# Sheet1.net
KiCad netlist of a schematic drawn in Altium Designer
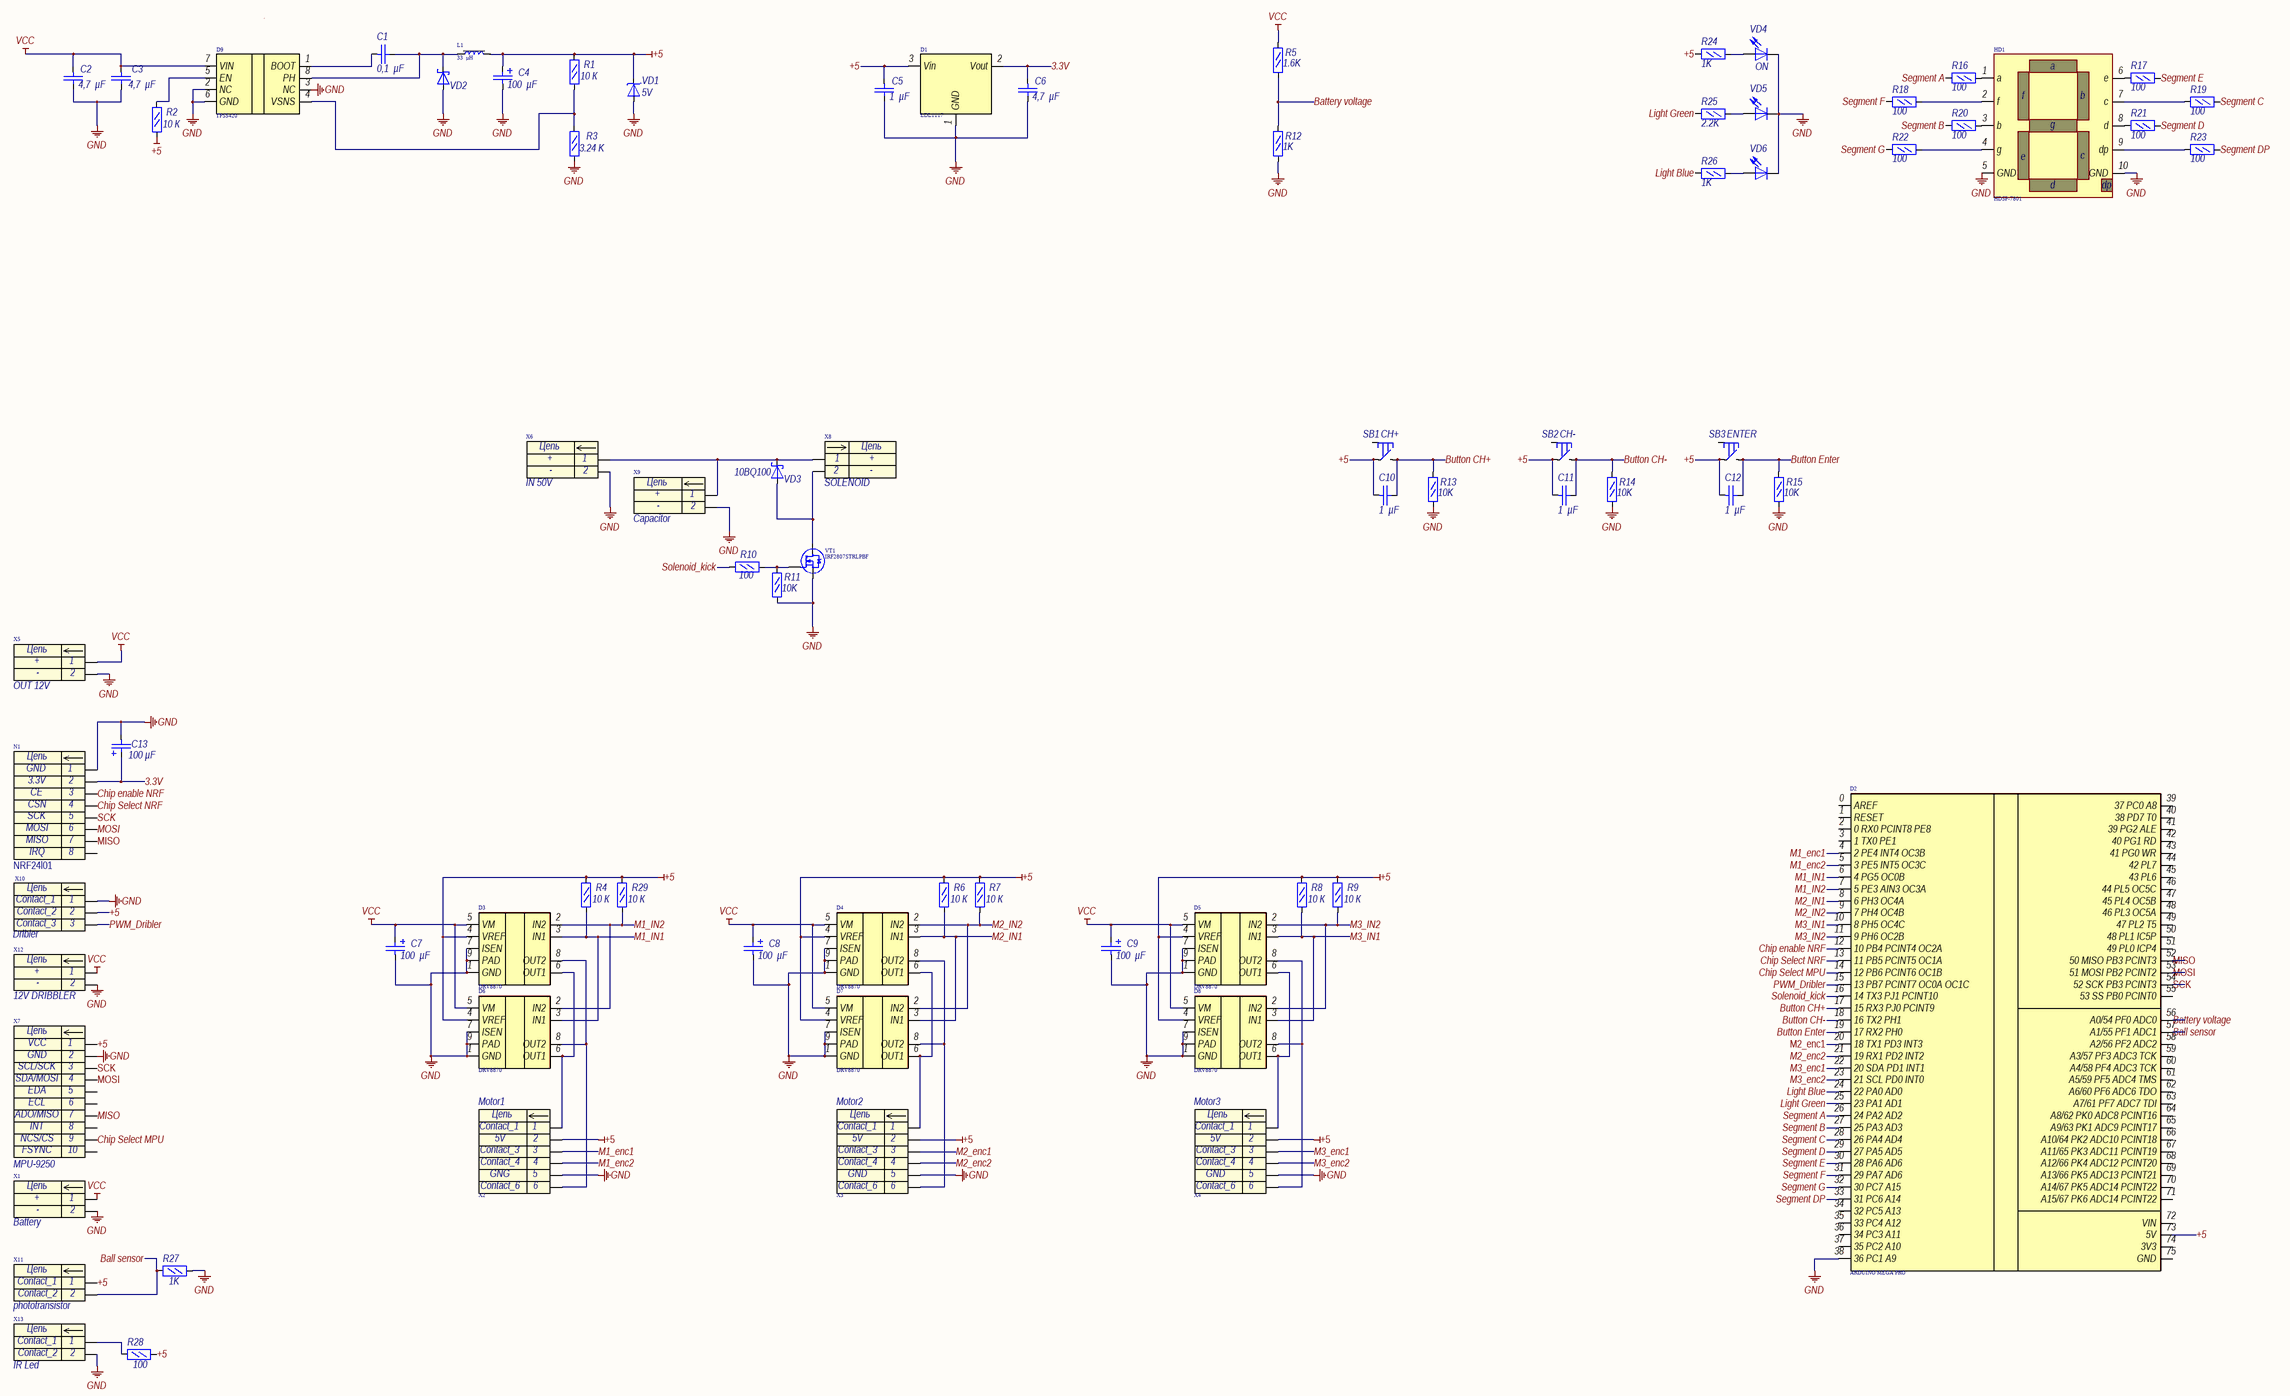
[diagram p0: Sheet1.SchDoc]

(export (version "E")
  (design (tool "Eeschema 10.0.6"))
  (components
    (comp (ref "C1")
      (value "0,1  µF")
      (footprint "LibPCB:NPC0805")
      (description "Конденсатор кер.")
      (libsource (lib "LibSCH") (part "Capacitor ceramic"))
    )
    (comp (ref "C2")
      (value "4,7  µF")
      (footprint "LibPCB:NPC0805")
      (description "Конденсатор кер.")
      (libsource (lib "LibSCH") (part "Capacitor ceramic"))
    )
    (comp (ref "C3")
      (value "4,7  µF")
      (footprint "LibPCB:NPC0805")
      (description "Конденсатор кер.")
      (libsource (lib "LibSCH") (part "Capacitor ceramic"))
    )
    (comp (ref "C4")
      (value "100  µF")
      (footprint "TANTAL CAPACITOR C")
      (description "Конденсатор пол.")
      (libsource (lib "LibSCH") (part "Capacitor tantal"))
    )
    (comp (ref "C5")
      (value "1  µF")
      (footprint "LibPCB:NPC0805")
      (description "Конденсатор кер.")
      (libsource (lib "LibSCH") (part "Capacitor ceramic"))
    )
    (comp (ref "C6")
      (value "4,7  µF")
      (footprint "LibPCB:NPC0805")
      (description "Конденсатор кер.")
      (libsource (lib "LibSCH") (part "Capacitor ceramic"))
    )
    (comp (ref "C7")
      (value "100  µF")
      (footprint "TANTAL CAPACITOR C")
      (description "Конденсатор пол.")
      (libsource (lib "LibSCH") (part "Capacitor tantal"))
    )
    (comp (ref "C8")
      (value "100  µF")
      (footprint "TANTAL CAPACITOR C")
      (description "Конденсатор пол.")
      (libsource (lib "LibSCH") (part "Capacitor tantal"))
    )
    (comp (ref "C9")
      (value "100  µF")
      (footprint "TANTAL CAPACITOR C")
      (description "Конденсатор пол.")
      (libsource (lib "LibSCH") (part "Capacitor tantal"))
    )
    (comp (ref "C10")
      (value "1  µF")
      (footprint "LibPCB:NPC0805")
      (description "Конденсатор кер.")
      (libsource (lib "LibSCH") (part "Capacitor ceramic"))
    )
    (comp (ref "C11")
      (value "1  µF")
      (footprint "LibPCB:NPC0805")
      (description "Конденсатор кер.")
      (libsource (lib "LibSCH") (part "Capacitor ceramic"))
    )
    (comp (ref "C12")
      (value "1  µF")
      (footprint "LibPCB:NPC0805")
      (description "Конденсатор кер.")
      (libsource (lib "LibSCH") (part "Capacitor ceramic"))
    )
    (comp (ref "C13")
      (value "100 µF")
      (footprint "TANTAL CAPACITOR D")
      (description "Конденсатор пол.")
      (libsource (lib "LibSCH") (part "Capacitor tantal"))
    )
    (comp (ref "D1")
      (value "LDL1117")
      (footprint "SOT223_M")
      (description "DC-DC преобразователь")
      (libsource (lib "LibSCH") (part "LDL1117"))
    )
    (comp (ref "D2")
      (value "ARDUINO MEGA PRO")
      (footprint "Arduino mega pro")
      (description "Микроконтроллер")
      (libsource (lib "LibSCH") (part "ARDUINO MEGA PRO"))
    )
    (comp (ref "D3")
      (value "DRV8870")
      (footprint "SOIC8 WITH THERMAL PAD")
      (description "Драйвер моторов")
      (libsource (lib "LibSCH") (part "DRV8870"))
    )
    (comp (ref "D4")
      (value "DRV8870")
      (footprint "SOIC8 WITH THERMAL PAD")
      (description "Драйвер моторов")
      (libsource (lib "LibSCH") (part "DRV8870"))
    )
    (comp (ref "D5")
      (value "DRV8870")
      (footprint "SOIC8 WITH THERMAL PAD")
      (description "Драйвер моторов")
      (libsource (lib "LibSCH") (part "DRV8870"))
    )
    (comp (ref "D6")
      (value "DRV8870")
      (footprint "SOIC8 WITH THERMAL PAD")
      (description "Драйвер моторов")
      (libsource (lib "LibSCH") (part "DRV8870"))
    )
    (comp (ref "D7")
      (value "DRV8870")
      (footprint "SOIC8 WITH THERMAL PAD")
      (description "Драйвер моторов")
      (libsource (lib "LibSCH") (part "DRV8870"))
    )
    (comp (ref "D8")
      (value "DRV8870")
      (footprint "SOIC8 WITH THERMAL PAD")
      (description "Драйвер моторов")
      (libsource (lib "LibSCH") (part "DRV8870"))
    )
    (comp (ref "D9") (value "TPS5420") (footprint "LibPCB:SO8") (libsource (lib "LibSCH") (part "TPS5420")))
    (comp (ref "HD1")
      (value "HDSP-7801")
      (footprint "HDSP-7801")
      (libsource (lib "LibSCH") (part "HDSP-7801"))
    )
    (comp (ref "L1")
      (value "33  µH")
      (footprint "LibPCB:IND: B82472G")
      (libsource (lib "LibSCH") (part "Throttle B82472G"))
    )
    (comp (ref "N1") (value "NRF24l01") (footprint "NRF24l01") (libsource (lib "LibSCH") (part "NRF24l01")))
    (comp (ref "R1")
      (value "10 К")
      (footprint "LibPCB:R0805")
      (description "Резистор  0,125Вт")
      (libsource (lib "") (part "Резистор  0,125Вт_1"))
    )
    (comp (ref "R2")
      (value "10 К")
      (footprint "LibPCB:R0805")
      (description "Резистор  0,125Вт")
      (libsource (lib "") (part "Резистор  0,125Вт_1"))
    )
    (comp (ref "R3")
      (value "3.24 K")
      (footprint "LibPCB:R0805")
      (description "Резистор  0,125Вт")
      (libsource (lib "") (part "Резистор  0,125Вт_1"))
    )
    (comp (ref "R4")
      (value "10 К")
      (footprint "LibPCB:R0805")
      (description "Резистор  0,125Вт")
      (libsource (lib "") (part "Резистор  0,125Вт_1"))
    )
    (comp (ref "R5")
      (value "1.6K")
      (footprint "LibPCB:R0805")
      (description "Резистор  0,125Вт")
      (libsource (lib "") (part "Резистор  0,125Вт_1"))
    )
    (comp (ref "R6")
      (value "10 К")
      (footprint "LibPCB:R0805")
      (description "Резистор  0,125Вт")
      (libsource (lib "") (part "Резистор  0,125Вт_1"))
    )
    (comp (ref "R7")
      (value "10 К")
      (footprint "LibPCB:R0805")
      (description "Резистор  0,125Вт")
      (libsource (lib "") (part "Резистор  0,125Вт_1"))
    )
    (comp (ref "R8")
      (value "10 К")
      (footprint "LibPCB:R0805")
      (description "Резистор  0,125Вт")
      (libsource (lib "") (part "Резистор  0,125Вт_1"))
    )
    (comp (ref "R9")
      (value "10 К")
      (footprint "LibPCB:R0805")
      (description "Резистор  0,125Вт")
      (libsource (lib "") (part "Резистор  0,125Вт_1"))
    )
    (comp (ref "R10")
      (value "100")
      (footprint "LibPCB:R0805")
      (description "Резистор  0,125Вт")
      (libsource (lib "") (part "Резистор  0,125Вт_2"))
    )
    (comp (ref "R11")
      (value "10K")
      (footprint "LibPCB:R0805")
      (description "Резистор  0,125Вт")
      (libsource (lib "") (part "Резистор  0,125Вт_1"))
    )
    (comp (ref "R12")
      (value "1K")
      (footprint "LibPCB:R0805")
      (description "Резистор  0,125Вт")
      (libsource (lib "") (part "Резистор  0,125Вт_1"))
    )
    (comp (ref "R13")
      (value "10K")
      (footprint "LibPCB:R0805")
      (description "Резистор  0,125Вт")
      (libsource (lib "") (part "Резистор  0,125Вт_1"))
    )
    (comp (ref "R14")
      (value "10K")
      (footprint "LibPCB:R0805")
      (description "Резистор  0,125Вт")
      (libsource (lib "") (part "Резистор  0,125Вт_1"))
    )
    (comp (ref "R15")
      (value "10K")
      (footprint "LibPCB:R0805")
      (description "Резистор  0,125Вт")
      (libsource (lib "") (part "Резистор  0,125Вт_1"))
    )
    (comp (ref "R16")
      (value "100")
      (footprint "LibPCB:R0805")
      (description "Резистор  0,125Вт")
      (libsource (lib "LibSCH") (part "Резистор  0,125Вт"))
    )
    (comp (ref "R17")
      (value "100")
      (footprint "LibPCB:R0805")
      (description "Резистор  0,125Вт")
      (libsource (lib "LibSCH") (part "Резистор  0,125Вт"))
    )
    (comp (ref "R18")
      (value "100")
      (footprint "LibPCB:R0805")
      (description "Резистор  0,125Вт")
      (libsource (lib "LibSCH") (part "Резистор  0,125Вт"))
    )
    (comp (ref "R19")
      (value "100")
      (footprint "LibPCB:R0805")
      (description "Резистор  0,125Вт")
      (libsource (lib "LibSCH") (part "Резистор  0,125Вт"))
    )
    (comp (ref "R20")
      (value "100")
      (footprint "LibPCB:R0805")
      (description "Резистор  0,125Вт")
      (libsource (lib "LibSCH") (part "Резистор  0,125Вт"))
    )
    (comp (ref "R21")
      (value "100")
      (footprint "LibPCB:R0805")
      (description "Резистор  0,125Вт")
      (libsource (lib "LibSCH") (part "Резистор  0,125Вт"))
    )
    (comp (ref "R22")
      (value "100")
      (footprint "LibPCB:R0805")
      (description "Резистор  0,125Вт")
      (libsource (lib "LibSCH") (part "Резистор  0,125Вт"))
    )
    (comp (ref "R23")
      (value "100")
      (footprint "LibPCB:R0805")
      (description "Резистор  0,125Вт")
      (libsource (lib "LibSCH") (part "Резистор  0,125Вт"))
    )
    (comp (ref "R24")
      (value "1K")
      (footprint "LibPCB:R0805")
      (description "Резистор  0,125Вт")
      (libsource (lib "LibSCH") (part "Резистор  0,125Вт"))
    )
    (comp (ref "R25")
      (value "2.2K")
      (footprint "LibPCB:R0805")
      (description "Резистор  0,125Вт")
      (libsource (lib "LibSCH") (part "Резистор  0,125Вт"))
    )
    (comp (ref "R26")
      (value "1K")
      (footprint "LibPCB:R0805")
      (description "Резистор  0,125Вт")
      (libsource (lib "LibSCH") (part "Резистор  0,125Вт"))
    )
    (comp (ref "R27")
      (value "1K")
      (footprint "LibPCB:R0805")
      (description "Резистор  0,125Вт")
      (libsource (lib "LibSCH") (part "Резистор  0,125Вт"))
    )
    (comp (ref "R28")
      (value "100")
      (footprint "LibPCB:R0805")
      (description "Резистор  0,125Вт")
      (libsource (lib "LibSCH") (part "Резистор  0,125Вт"))
    )
    (comp (ref "R29")
      (value "10 К")
      (footprint "LibPCB:R0805")
      (description "Резистор  0,125Вт")
      (libsource (lib "") (part "Резистор  0,125Вт_1"))
    )
    (comp (ref "SB1")
      (value "~")
      (footprint "1-1437565-6 WITH LABEL")
      (description "Кнопка без фиксации")
      (fields (field (name "FUNCTION") "CH+"))
      (libsource (lib "LibSCH") (part "Button_SMD"))
    )
    (comp (ref "SB2")
      (value "~")
      (footprint "1-1437565-6 WITH LABEL")
      (description "Кнопка без фиксации")
      (fields (field (name "FUNCTION") "CH-"))
      (libsource (lib "LibSCH") (part "Button_SMD"))
    )
    (comp (ref "SB3")
      (value "~")
      (footprint "1-1437565-6 WITH LABEL")
      (description "Кнопка без фиксации")
      (fields (field (name "FUNCTION") "ENTER"))
      (libsource (lib "LibSCH") (part "Button_SMD"))
    )
    (comp (ref "VD1")
      (value "5V")
      (footprint "LibPCB:DO-214AC")
      (description "Защитный диод (Супрессор)")
      (libsource (lib "LibSCH") (part "Diode TVS"))
    )
    (comp (ref "VD2")
      (value "~")
      (footprint "LibPCB:SOD123")
      (description "Диод Шоттки")
      (libsource (lib "LibSCH") (part "DiodeSchottky"))
    )
    (comp (ref "VD3")
      (value "10BQ100")
      (footprint "DO-214AA")
      (description "Диод Шоттки")
      (fields (field (name "NAME") "10BQ100"))
      (libsource (lib "LibSCH") (part "DiodeSchottky"))
    )
    (comp (ref "VD4")
      (value "ON")
      (footprint "LibPCB:0805_LED _RED")
      (description "Светодиод SMD")
      (fields (field (name "MANUFACTURER") "KGB"))
      (libsource (lib "LibSCH") (part "LED"))
    )
    (comp (ref "VD5")
      (value "~")
      (footprint "LibPCB:0805_LED _GREEN")
      (description "Светодиод SMD")
      (fields (field (name "MANUFACTURER") "KGB"))
      (libsource (lib "LibSCH") (part "LED"))
    )
    (comp (ref "VD6")
      (value "~")
      (footprint "LibPCB:0805_LED _BLUE")
      (description "Светодиод SMD")
      (fields (field (name "MANUFACTURER") "KGB"))
      (libsource (lib "LibSCH") (part "LED"))
    )
    (comp (ref "VT1")
      (value "IRF2807STRLPBF")
      (footprint "D2PAK")
      (description "N-канальный транзистор")
      (libsource (lib "LibSCH") (part "N_MOSFET"))
    )
    (comp (ref "X1")
      (value "Battery")
      (footprint "KLS2-301-5.00 WITH LABEL")
      (description "Разъем - 2 конт. вилка")
      (libsource (lib "LibSCH") (part "Header_2_plg"))
    )
    (comp (ref "X2")
      (value "Motor1")
      (footprint "LibPCB:PLS-6")
      (description "Разъем - 6 конт. вилка")
      (libsource (lib "LibSCH") (part "Header_6_plg"))
    )
    (comp (ref "X3")
      (value "Motor2")
      (footprint "LibPCB:PLS-6")
      (description "Разъем - 6 конт. вилка")
      (libsource (lib "LibSCH") (part "Header_6_plg"))
    )
    (comp (ref "X4")
      (value "Motor3")
      (footprint "LibPCB:PLS-6")
      (description "Разъем - 6 конт. вилка")
      (libsource (lib "LibSCH") (part "Header_6_plg"))
    )
    (comp (ref "X5")
      (value "OUT 12V")
      (footprint "KLS2-301-5.00 WITH LABEL")
      (description "Разъем - 2 конт. вилка")
      (libsource (lib "LibSCH") (part "Header_2_plg"))
    )
    (comp (ref "X6")
      (value "IN 50V")
      (footprint "KLS2-301-5.00 WITH LABEL")
      (description "Разъем - 2 конт. вилка")
      (libsource (lib "LibSCH") (part "Header_2_plg"))
    )
    (comp (ref "X7") (value "MPU-9250") (footprint "MPU-9250") (libsource (lib "LibSCH") (part "MPU-9250")))
    (comp (ref "X8")
      (value "SOLENOID")
      (footprint "KLS2-301-5.00 WITH LABEL")
      (description "Разъем - 2 конт. вилка")
      (libsource (lib "") (part "Header_2_plg_1"))
    )
    (comp (ref "X9")
      (value "Capacitor")
      (footprint "KLS2-301-5.00 WITH LABEL")
      (description "Разъем - 2 конт. вилка")
      (libsource (lib "LibSCH") (part "Header_2_plg"))
    )
    (comp (ref "X10")
      (value "Dribler")
      (footprint "LibPCB:PLS-3")
      (description "Разъем - 3 конт. вилка")
      (libsource (lib "LibSCH") (part "Header_3_plg"))
    )
    (comp (ref "X11")
      (value "phototransistor")
      (footprint "JST B2B-XH-A")
      (description "Разъем - 2 конт. вилка")
      (libsource (lib "LibSCH") (part "Header_2_plg"))
    )
    (comp (ref "X12")
      (value "12V DRIBBLER")
      (footprint "KLS2-301-5.00 WITH LABEL")
      (description "Разъем - 2 конт. вилка")
      (libsource (lib "LibSCH") (part "Header_2_plg"))
    )
    (comp (ref "X13")
      (value "IR Led")
      (footprint "JST B2B-XH-A")
      (description "Разъем - 2 конт. вилка")
      (libsource (lib "LibSCH") (part "Header_2_plg"))
    )
  )
  (nets
    (net (code "1") (name "+5") (class "Default")
      (node (ref "C10") (pin "2") (pinfunction "2_2") (pintype "passive"))
      (node (ref "C11") (pin "2") (pinfunction "2_2") (pintype "passive"))
      (node (ref "C12") (pin "2") (pinfunction "2_2") (pintype "passive"))
      (node (ref "C4") (pin "1") (pinfunction "1_1") (pintype "passive"))
      (node (ref "C5") (pin "2") (pinfunction "2_2") (pintype "passive"))
      (node (ref "D1") (pin "3") (pinfunction "Vin_3") (pintype "passive"))
      (node (ref "D2") (pin "73") (pinfunction "5V_73") (pintype "passive"))
      (node (ref "D3") (pin "4") (pinfunction "VREF_4") (pintype "passive"))
      (node (ref "D4") (pin "4") (pinfunction "VREF_4") (pintype "passive"))
      (node (ref "D5") (pin "4") (pinfunction "VREF_4") (pintype "passive"))
      (node (ref "D6") (pin "4") (pinfunction "VREF_4") (pintype "passive"))
      (node (ref "D7") (pin "4") (pinfunction "VREF_4") (pintype "passive"))
      (node (ref "D8") (pin "4") (pinfunction "VREF_4") (pintype "passive"))
      (node (ref "L1") (pin "1") (pinfunction "2_1") (pintype "passive"))
      (node (ref "R1") (pin "2") (pinfunction "2_2") (pintype "passive"))
      (node (ref "R2") (pin "1") (pinfunction "1_1") (pintype "passive"))
      (node (ref "R24") (pin "2") (pinfunction "2_2") (pintype "passive"))
      (node (ref "R28") (pin "1") (pinfunction "1_1") (pintype "passive"))
      (node (ref "R29") (pin "2") (pinfunction "2_2") (pintype "passive"))
      (node (ref "R4") (pin "2") (pinfunction "2_2") (pintype "passive"))
      (node (ref "R6") (pin "2") (pinfunction "2_2") (pintype "passive"))
      (node (ref "R7") (pin "2") (pinfunction "2_2") (pintype "passive"))
      (node (ref "R8") (pin "2") (pinfunction "2_2") (pintype "passive"))
      (node (ref "R9") (pin "2") (pinfunction "2_2") (pintype "passive"))
      (node (ref "SB1") (pin "1") (pinfunction "1_1") (pintype "passive"))
      (node (ref "SB2") (pin "1") (pinfunction "1_1") (pintype "passive"))
      (node (ref "SB3") (pin "1") (pinfunction "1_1") (pintype "passive"))
      (node (ref "VD1") (pin "1") (pinfunction "K_1") (pintype "passive"))
      (node (ref "X10") (pin "2") (pinfunction "2_2") (pintype "passive"))
      (node (ref "X11") (pin "1") (pinfunction "1_1") (pintype "passive"))
      (node (ref "X2") (pin "2") (pinfunction "2_2") (pintype "passive"))
      (node (ref "X3") (pin "2") (pinfunction "2_2") (pintype "passive"))
      (node (ref "X4") (pin "2") (pinfunction "2_2") (pintype "passive"))
      (node (ref "X7") (pin "1") (pinfunction "VCC_1") (pintype "passive"))
    )
    (net (code "2") (name "/3.3V") (class "Default")
      (node (ref "C13") (pin "1") (pinfunction "1_1") (pintype "passive"))
      (node (ref "C6") (pin "2") (pinfunction "2_2") (pintype "passive"))
      (node (ref "D1") (pin "2") (pinfunction "Vout_2") (pintype "passive"))
      (node (ref "N1") (pin "2") (pinfunction "2_2") (pintype "passive"))
    )
    (net (code "3") (name "/Ball sensor") (class "Default")
      (node (ref "D2") (pin "57") (pinfunction "A1/55_PF1_ADC1_57") (pintype "passive"))
      (node (ref "R27") (pin "2") (pinfunction "2_2") (pintype "passive"))
      (node (ref "X11") (pin "2") (pinfunction "2_2") (pintype "passive"))
    )
    (net (code "4") (name "/Battery voltage") (class "Default")
      (node (ref "D2") (pin "56") (pinfunction "A0/54_PF0_ADC0_56") (pintype "passive"))
      (node (ref "R12") (pin "2") (pinfunction "2_2") (pintype "passive"))
      (node (ref "R5") (pin "1") (pinfunction "1_1") (pintype "passive"))
    )
    (net (code "5") (name "/Button CH+") (class "Default")
      (node (ref "C10") (pin "1") (pinfunction "1_1") (pintype "passive"))
      (node (ref "D2") (pin "17") (pinfunction "15_RX3_PJ0_PCINT9_17") (pintype "passive"))
      (node (ref "R13") (pin "2") (pinfunction "2_2") (pintype "passive"))
      (node (ref "SB1") (pin "2") (pinfunction "2_2") (pintype "passive"))
    )
    (net (code "6") (name "/Button CH-") (class "Default")
      (node (ref "C11") (pin "1") (pinfunction "1_1") (pintype "passive"))
      (node (ref "D2") (pin "18") (pinfunction "16_TX2_PH1_18") (pintype "passive"))
      (node (ref "R14") (pin "2") (pinfunction "2_2") (pintype "passive"))
      (node (ref "SB2") (pin "2") (pinfunction "2_2") (pintype "passive"))
    )
    (net (code "7") (name "/Button Enter") (class "Default")
      (node (ref "C12") (pin "1") (pinfunction "1_1") (pintype "passive"))
      (node (ref "D2") (pin "19") (pinfunction "17_RX2_PH0_19") (pintype "passive"))
      (node (ref "R15") (pin "2") (pinfunction "2_2") (pintype "passive"))
      (node (ref "SB3") (pin "2") (pinfunction "2_2") (pintype "passive"))
    )
    (net (code "8") (name "/Chip Select MPU") (class "Default")
      (node (ref "D2") (pin "14") (pinfunction "12_PB6_PCINT6_OC1B_14") (pintype "passive"))
      (node (ref "X7") (pin "9") (pinfunction "9_9") (pintype "passive"))
    )
    (net (code "9") (name "/Chip Select NRF") (class "Default")
      (node (ref "D2") (pin "13") (pinfunction "11_PB5_PCINT5_OC1A_13") (pintype "passive"))
      (node (ref "N1") (pin "4") (pinfunction "4_4") (pintype "passive"))
    )
    (net (code "10") (name "/Chip enable NRF") (class "Default")
      (node (ref "D2") (pin "12") (pinfunction "10_PB4_PCINT4_OC2A_12") (pintype "passive"))
      (node (ref "N1") (pin "3") (pinfunction "3_3") (pintype "passive"))
    )
    (net (code "11") (name "/Light Blue") (class "Default")
      (node (ref "D2") (pin "24") (pinfunction "22_PA0_AD0_24") (pintype "passive"))
      (node (ref "R26") (pin "2") (pinfunction "2_2") (pintype "passive"))
    )
    (net (code "12") (name "/Light Green") (class "Default")
      (node (ref "D2") (pin "25") (pinfunction "23_PA1_AD1_25") (pintype "passive"))
      (node (ref "R25") (pin "2") (pinfunction "2_2") (pintype "passive"))
    )
    (net (code "13") (name "/M1_IN1") (class "Default")
      (node (ref "D2") (pin "6") (pinfunction "4_PG5_OC0B_6") (pintype "passive"))
      (node (ref "D3") (pin "3") (pinfunction "IN1_3") (pintype "passive"))
      (node (ref "D6") (pin "3") (pinfunction "IN1_3") (pintype "passive"))
      (node (ref "R4") (pin "1") (pinfunction "1_1") (pintype "passive"))
    )
    (net (code "14") (name "/M1_IN2") (class "Default")
      (node (ref "D2") (pin "7") (pinfunction "5_PE3_AIN3_OC3A_7") (pintype "passive"))
      (node (ref "D3") (pin "2") (pinfunction "IN2_2") (pintype "passive"))
      (node (ref "D6") (pin "2") (pinfunction "IN2_2") (pintype "passive"))
      (node (ref "R29") (pin "1") (pinfunction "1_1") (pintype "passive"))
    )
    (net (code "15") (name "/M1_enc1") (class "Default")
      (node (ref "D2") (pin "4") (pinfunction "2_PE4_INT4_OC3B_4") (pintype "passive"))
      (node (ref "X2") (pin "3") (pinfunction "3_3") (pintype "passive"))
    )
    (net (code "16") (name "/M1_enc2") (class "Default")
      (node (ref "D2") (pin "5") (pinfunction "3_PE5_INT5_OC3C_5") (pintype "passive"))
      (node (ref "X2") (pin "4") (pinfunction "4_4") (pintype "passive"))
    )
    (net (code "17") (name "/M2_IN1") (class "Default")
      (node (ref "D2") (pin "8") (pinfunction "6_PH3_OC4A_8") (pintype "passive"))
      (node (ref "D4") (pin "3") (pinfunction "IN1_3") (pintype "passive"))
      (node (ref "D7") (pin "3") (pinfunction "IN1_3") (pintype "passive"))
      (node (ref "R6") (pin "1") (pinfunction "1_1") (pintype "passive"))
    )
    (net (code "18") (name "/M2_IN2") (class "Default")
      (node (ref "D2") (pin "9") (pinfunction "7_PH4_OC4B_9") (pintype "passive"))
      (node (ref "D4") (pin "2") (pinfunction "IN2_2") (pintype "passive"))
      (node (ref "D7") (pin "2") (pinfunction "IN2_2") (pintype "passive"))
      (node (ref "R7") (pin "1") (pinfunction "1_1") (pintype "passive"))
    )
    (net (code "19") (name "/M2_enc1") (class "Default")
      (node (ref "D2") (pin "20") (pinfunction "18_TX1_PD3_INT3_20") (pintype "passive"))
      (node (ref "X3") (pin "3") (pinfunction "3_3") (pintype "passive"))
    )
    (net (code "20") (name "/M2_enc2") (class "Default")
      (node (ref "D2") (pin "21") (pinfunction "19_RX1_PD2_INT2_21") (pintype "passive"))
      (node (ref "X3") (pin "4") (pinfunction "4_4") (pintype "passive"))
    )
    (net (code "21") (name "/M3_IN1") (class "Default")
      (node (ref "D2") (pin "10") (pinfunction "8_PH5_OC4C_10") (pintype "passive"))
      (node (ref "D5") (pin "3") (pinfunction "IN1_3") (pintype "passive"))
      (node (ref "D8") (pin "3") (pinfunction "IN1_3") (pintype "passive"))
      (node (ref "R8") (pin "1") (pinfunction "1_1") (pintype "passive"))
    )
    (net (code "22") (name "/M3_IN2") (class "Default")
      (node (ref "D2") (pin "11") (pinfunction "9_PH6_OC2B_11") (pintype "passive"))
      (node (ref "D5") (pin "2") (pinfunction "IN2_2") (pintype "passive"))
      (node (ref "D8") (pin "2") (pinfunction "IN2_2") (pintype "passive"))
      (node (ref "R9") (pin "1") (pinfunction "1_1") (pintype "passive"))
    )
    (net (code "23") (name "/M3_enc1") (class "Default")
      (node (ref "D2") (pin "22") (pinfunction "20_SDA_PD1_INT1_22") (pintype "passive"))
      (node (ref "X4") (pin "3") (pinfunction "3_3") (pintype "passive"))
    )
    (net (code "24") (name "/M3_enc2") (class "Default")
      (node (ref "D2") (pin "23") (pinfunction "21_SCL_PD0_INT0_23") (pintype "passive"))
      (node (ref "X4") (pin "4") (pinfunction "4_4") (pintype "passive"))
    )
    (net (code "25") (name "/MISO") (class "Default")
      (node (ref "D2") (pin "52") (pinfunction "50_MISO_PB3_PCINT3_52") (pintype "passive"))
      (node (ref "N1") (pin "7") (pinfunction "7_7") (pintype "passive"))
      (node (ref "X7") (pin "7") (pinfunction "7_7") (pintype "passive"))
    )
    (net (code "26") (name "/MOSI") (class "Default")
      (node (ref "D2") (pin "53") (pinfunction "51_MOSI_PB2_PCINT2_53") (pintype "passive"))
      (node (ref "N1") (pin "6") (pinfunction "6_6") (pintype "passive"))
      (node (ref "X7") (pin "4") (pinfunction "4_4") (pintype "passive"))
    )
    (net (code "27") (name "/PWM_Dribler") (class "Default")
      (node (ref "D2") (pin "15") (pinfunction "13_PB7_PCINT7_OC0A_OC1C_15") (pintype "passive"))
      (node (ref "X10") (pin "3") (pinfunction "3_3") (pintype "passive"))
    )
    (net (code "28") (name "/SCK") (class "Default")
      (node (ref "D2") (pin "54") (pinfunction "52_SCK_PB3_PCINT3_54") (pintype "passive"))
      (node (ref "N1") (pin "5") (pinfunction "5_5") (pintype "passive"))
      (node (ref "X7") (pin "3") (pinfunction "3_3") (pintype "passive"))
    )
    (net (code "29") (name "/Segment A") (class "Default")
      (node (ref "D2") (pin "26") (pinfunction "24_PA2_AD2_26") (pintype "passive"))
      (node (ref "R16") (pin "2") (pinfunction "2_2") (pintype "passive"))
    )
    (net (code "30") (name "/Segment B") (class "Default")
      (node (ref "D2") (pin "27") (pinfunction "25_PA3_AD3_27") (pintype "passive"))
      (node (ref "R20") (pin "2") (pinfunction "2_2") (pintype "passive"))
    )
    (net (code "31") (name "/Segment C") (class "Default")
      (node (ref "D2") (pin "28") (pinfunction "26_PA4_AD4_28") (pintype "passive"))
      (node (ref "R19") (pin "1") (pinfunction "1_1") (pintype "passive"))
    )
    (net (code "32") (name "/Segment D") (class "Default")
      (node (ref "D2") (pin "29") (pinfunction "27_PA5_AD5_29") (pintype "passive"))
      (node (ref "R21") (pin "1") (pinfunction "1_1") (pintype "passive"))
    )
    (net (code "33") (name "/Segment DP") (class "Default")
      (node (ref "D2") (pin "33") (pinfunction "31_PC6_A14_33") (pintype "passive"))
      (node (ref "R23") (pin "1") (pinfunction "1_1") (pintype "passive"))
    )
    (net (code "34") (name "/Segment E") (class "Default")
      (node (ref "D2") (pin "30") (pinfunction "28_PA6_AD6_30") (pintype "passive"))
      (node (ref "R17") (pin "1") (pinfunction "1_1") (pintype "passive"))
    )
    (net (code "35") (name "/Segment F") (class "Default")
      (node (ref "D2") (pin "31") (pinfunction "29_PA7_AD6_31") (pintype "passive"))
      (node (ref "R18") (pin "2") (pinfunction "2_2") (pintype "passive"))
    )
    (net (code "36") (name "/Segment G") (class "Default")
      (node (ref "D2") (pin "32") (pinfunction "30_PC7_A15_32") (pintype "passive"))
      (node (ref "R22") (pin "2") (pinfunction "2_2") (pintype "passive"))
    )
    (net (code "37") (name "/Solenoid_kick") (class "Default")
      (node (ref "D2") (pin "16") (pinfunction "14_TX3_PJ1_PCINT10_16") (pintype "passive"))
      (node (ref "R10") (pin "1") (pinfunction "1_1") (pintype "passive"))
    )
    (net (code "38") (name "GND") (class "Default")
      (node (ref "C13") (pin "2") (pinfunction "2_2") (pintype "passive"))
      (node (ref "C2") (pin "1") (pinfunction "1_1") (pintype "passive"))
      (node (ref "C3") (pin "1") (pinfunction "1_1") (pintype "passive"))
      (node (ref "C4") (pin "2") (pinfunction "2_2") (pintype "passive"))
      (node (ref "C5") (pin "1") (pinfunction "1_1") (pintype "passive"))
      (node (ref "C6") (pin "1") (pinfunction "1_1") (pintype "passive"))
      (node (ref "C7") (pin "2") (pinfunction "2_2") (pintype "passive"))
      (node (ref "C8") (pin "2") (pinfunction "2_2") (pintype "passive"))
      (node (ref "C9") (pin "2") (pinfunction "2_2") (pintype "passive"))
      (node (ref "D1") (pin "1") (pinfunction "GND_1") (pintype "passive"))
      (node (ref "D2") (pin "38") (pinfunction "36_PC1_A9_38") (pintype "passive"))
      (node (ref "D3") (pin "1") (pinfunction "GND_1") (pintype "passive"))
      (node (ref "D3") (pin "7") (pinfunction "ISEN_7") (pintype "passive"))
      (node (ref "D3") (pin "9") (pinfunction "PAD_9") (pintype "passive"))
      (node (ref "D4") (pin "1") (pinfunction "GND_1") (pintype "passive"))
      (node (ref "D4") (pin "7") (pinfunction "ISEN_7") (pintype "passive"))
      (node (ref "D4") (pin "9") (pinfunction "PAD_9") (pintype "passive"))
      (node (ref "D5") (pin "1") (pinfunction "GND_1") (pintype "passive"))
      (node (ref "D5") (pin "7") (pinfunction "ISEN_7") (pintype "passive"))
      (node (ref "D5") (pin "9") (pinfunction "PAD_9") (pintype "passive"))
      (node (ref "D6") (pin "1") (pinfunction "GND_1") (pintype "passive"))
      (node (ref "D6") (pin "7") (pinfunction "ISEN_7") (pintype "passive"))
      (node (ref "D6") (pin "9") (pinfunction "PAD_9") (pintype "passive"))
      (node (ref "D7") (pin "1") (pinfunction "GND_1") (pintype "passive"))
      (node (ref "D7") (pin "7") (pinfunction "ISEN_7") (pintype "passive"))
      (node (ref "D7") (pin "9") (pinfunction "PAD_9") (pintype "passive"))
      (node (ref "D8") (pin "1") (pinfunction "GND_1") (pintype "passive"))
      (node (ref "D8") (pin "7") (pinfunction "ISEN_7") (pintype "passive"))
      (node (ref "D8") (pin "9") (pinfunction "PAD_9") (pintype "passive"))
      (node (ref "D9") (pin "2") (pinfunction "NC_2") (pintype "passive"))
      (node (ref "D9") (pin "3") (pinfunction "NC_3") (pintype "passive"))
      (node (ref "D9") (pin "6") (pinfunction "GND_6") (pintype "passive"))
      (node (ref "HD1") (pin "10") (pinfunction "GND_10") (pintype "passive"))
      (node (ref "HD1") (pin "5") (pinfunction "GND_5") (pintype "passive"))
      (node (ref "N1") (pin "1") (pinfunction "1_1") (pintype "passive"))
      (node (ref "R11") (pin "1") (pinfunction "1_1") (pintype "passive"))
      (node (ref "R12") (pin "1") (pinfunction "1_1") (pintype "passive"))
      (node (ref "R13") (pin "1") (pinfunction "1_1") (pintype "passive"))
      (node (ref "R14") (pin "1") (pinfunction "1_1") (pintype "passive"))
      (node (ref "R15") (pin "1") (pinfunction "1_1") (pintype "passive"))
      (node (ref "R27") (pin "1") (pinfunction "1_1") (pintype "passive"))
      (node (ref "R3") (pin "1") (pinfunction "1_1") (pintype "passive"))
      (node (ref "VD1") (pin "2") (pinfunction "A_2") (pintype "passive"))
      (node (ref "VD2") (pin "2") (pinfunction "A_2") (pintype "passive"))
      (node (ref "VD4") (pin "1") (pinfunction "K_1") (pintype "passive"))
      (node (ref "VD5") (pin "1") (pinfunction "K_1") (pintype "passive"))
      (node (ref "VD6") (pin "1") (pinfunction "K_1") (pintype "passive"))
      (node (ref "VT1") (pin "3") (pinfunction "S_3") (pintype "passive"))
      (node (ref "X1") (pin "2") (pinfunction "2_2") (pintype "passive"))
      (node (ref "X10") (pin "1") (pinfunction "1_1") (pintype "passive"))
      (node (ref "X12") (pin "2") (pinfunction "2_2") (pintype "passive"))
      (node (ref "X13") (pin "2") (pinfunction "2_2") (pintype "passive"))
      (node (ref "X2") (pin "5") (pinfunction "5_5") (pintype "passive"))
      (node (ref "X3") (pin "5") (pinfunction "5_5") (pintype "passive"))
      (node (ref "X4") (pin "5") (pinfunction "5_5") (pintype "passive"))
      (node (ref "X5") (pin "2") (pinfunction "2_2") (pintype "passive"))
      (node (ref "X6") (pin "2") (pinfunction "2_2") (pintype "passive"))
      (node (ref "X7") (pin "2") (pinfunction "2_2") (pintype "passive"))
      (node (ref "X9") (pin "2") (pinfunction "2_2") (pintype "passive"))
    )
    (net (code "39") (name "Net-(D3-OUT1)") (class "Default")
      (node (ref "D3") (pin "6") (pinfunction "OUT1_6") (pintype "passive"))
      (node (ref "D6") (pin "6") (pinfunction "OUT1_6") (pintype "passive"))
      (node (ref "X2") (pin "1") (pinfunction "1_1") (pintype "passive"))
    )
    (net (code "40") (name "Net-(D3-OUT2)") (class "Default")
      (node (ref "D3") (pin "8") (pinfunction "OUT2_8") (pintype "passive"))
      (node (ref "D6") (pin "8") (pinfunction "OUT2_8") (pintype "passive"))
      (node (ref "X2") (pin "6") (pinfunction "6_6") (pintype "passive"))
    )
    (net (code "41") (name "Net-(D4-OUT1)") (class "Default")
      (node (ref "D4") (pin "6") (pinfunction "OUT1_6") (pintype "passive"))
      (node (ref "D7") (pin "6") (pinfunction "OUT1_6") (pintype "passive"))
      (node (ref "X3") (pin "1") (pinfunction "1_1") (pintype "passive"))
    )
    (net (code "42") (name "Net-(D4-OUT2)") (class "Default")
      (node (ref "D4") (pin "8") (pinfunction "OUT2_8") (pintype "passive"))
      (node (ref "D7") (pin "8") (pinfunction "OUT2_8") (pintype "passive"))
      (node (ref "X3") (pin "6") (pinfunction "6_6") (pintype "passive"))
    )
    (net (code "43") (name "Net-(D5-OUT1)") (class "Default")
      (node (ref "D5") (pin "6") (pinfunction "OUT1_6") (pintype "passive"))
      (node (ref "D8") (pin "6") (pinfunction "OUT1_6") (pintype "passive"))
      (node (ref "X4") (pin "1") (pinfunction "1_1") (pintype "passive"))
    )
    (net (code "44") (name "Net-(D5-OUT2)") (class "Default")
      (node (ref "D5") (pin "8") (pinfunction "OUT2_8") (pintype "passive"))
      (node (ref "D8") (pin "8") (pinfunction "OUT2_8") (pintype "passive"))
      (node (ref "X4") (pin "6") (pinfunction "6_6") (pintype "passive"))
    )
    (net (code "45") (name "Net-(D9-BOOT)") (class "Default")
      (node (ref "C1") (pin "2") (pinfunction "2_2") (pintype "passive"))
      (node (ref "D9") (pin "1") (pinfunction "BOOT_1") (pintype "passive"))
    )
    (net (code "46") (name "Net-(D9-EN)") (class "Default")
      (node (ref "D9") (pin "5") (pinfunction "EN_5") (pintype "passive"))
      (node (ref "R2") (pin "2") (pinfunction "2_2") (pintype "passive"))
    )
    (net (code "47") (name "Net-(D9-PH)") (class "Default")
      (node (ref "C1") (pin "1") (pinfunction "1_1") (pintype "passive"))
      (node (ref "D9") (pin "8") (pinfunction "PH_8") (pintype "passive"))
      (node (ref "L1") (pin "2") (pinfunction "2_2") (pintype "passive"))
      (node (ref "VD2") (pin "1") (pinfunction "K_1") (pintype "passive"))
    )
    (net (code "48") (name "Net-(D9-VSNS)") (class "Default")
      (node (ref "D9") (pin "4") (pinfunction "VSNS_4") (pintype "passive"))
      (node (ref "R1") (pin "1") (pinfunction "1_1") (pintype "passive"))
      (node (ref "R3") (pin "2") (pinfunction "2_2") (pintype "passive"))
    )
    (net (code "49") (name "Net-(HD1-a)") (class "Default")
      (node (ref "HD1") (pin "1") (pinfunction "a_1") (pintype "passive"))
      (node (ref "R16") (pin "1") (pinfunction "1_1") (pintype "passive"))
    )
    (net (code "50") (name "Net-(HD1-b)") (class "Default")
      (node (ref "HD1") (pin "3") (pinfunction "b_3") (pintype "passive"))
      (node (ref "R20") (pin "1") (pinfunction "1_1") (pintype "passive"))
    )
    (net (code "51") (name "Net-(HD1-c)") (class "Default")
      (node (ref "HD1") (pin "7") (pinfunction "c_7") (pintype "passive"))
      (node (ref "R19") (pin "2") (pinfunction "2_2") (pintype "passive"))
    )
    (net (code "52") (name "Net-(HD1-d)") (class "Default")
      (node (ref "HD1") (pin "8") (pinfunction "d_8") (pintype "passive"))
      (node (ref "R21") (pin "2") (pinfunction "2_2") (pintype "passive"))
    )
    (net (code "53") (name "Net-(HD1-dp)") (class "Default")
      (node (ref "HD1") (pin "9") (pinfunction "dp_9") (pintype "passive"))
      (node (ref "R23") (pin "2") (pinfunction "2_2") (pintype "passive"))
    )
    (net (code "54") (name "Net-(HD1-e)") (class "Default")
      (node (ref "HD1") (pin "6") (pinfunction "e_6") (pintype "passive"))
      (node (ref "R17") (pin "2") (pinfunction "2_2") (pintype "passive"))
    )
    (net (code "55") (name "Net-(HD1-f)") (class "Default")
      (node (ref "HD1") (pin "2") (pinfunction "f_2") (pintype "passive"))
      (node (ref "R18") (pin "1") (pinfunction "1_1") (pintype "passive"))
    )
    (net (code "56") (name "Net-(HD1-g)") (class "Default")
      (node (ref "HD1") (pin "4") (pinfunction "g_4") (pintype "passive"))
      (node (ref "R22") (pin "1") (pinfunction "1_1") (pintype "passive"))
    )
    (net (code "57") (name "Net-(R28-Pad2)") (class "Default")
      (node (ref "R28") (pin "2") (pinfunction "2_2") (pintype "passive"))
      (node (ref "X13") (pin "1") (pinfunction "1_1") (pintype "passive"))
    )
    (net (code "58") (name "Net-(VD3-A)") (class "Default")
      (node (ref "VD3") (pin "2") (pinfunction "A_2") (pintype "passive"))
      (node (ref "VT1") (pin "2") (pinfunction "D_2") (pintype "passive"))
      (node (ref "X8") (pin "2") (pinfunction "2_2") (pintype "passive"))
    )
    (net (code "59") (name "Net-(VD3-K)") (class "Default")
      (node (ref "VD3") (pin "1") (pinfunction "K_1") (pintype "passive"))
      (node (ref "X6") (pin "1") (pinfunction "1_1") (pintype "passive"))
      (node (ref "X8") (pin "1") (pinfunction "1_1") (pintype "passive"))
      (node (ref "X9") (pin "1") (pinfunction "1_1") (pintype "passive"))
    )
    (net (code "60") (name "Net-(VD4-A)") (class "Default")
      (node (ref "R24") (pin "1") (pinfunction "1_1") (pintype "passive"))
      (node (ref "VD4") (pin "2") (pinfunction "A_2") (pintype "passive"))
    )
    (net (code "61") (name "Net-(VD5-A)") (class "Default")
      (node (ref "R25") (pin "1") (pinfunction "1_1") (pintype "passive"))
      (node (ref "VD5") (pin "2") (pinfunction "A_2") (pintype "passive"))
    )
    (net (code "62") (name "Net-(VD6-A)") (class "Default")
      (node (ref "R26") (pin "1") (pinfunction "1_1") (pintype "passive"))
      (node (ref "VD6") (pin "2") (pinfunction "A_2") (pintype "passive"))
    )
    (net (code "63") (name "Net-(VT1-G)") (class "Default")
      (node (ref "R10") (pin "2") (pinfunction "2_2") (pintype "passive"))
      (node (ref "R11") (pin "2") (pinfunction "2_2") (pintype "passive"))
      (node (ref "VT1") (pin "1") (pinfunction "G_1") (pintype "passive"))
    )
    (net (code "64") (name "VCC") (class "Default")
      (node (ref "C2") (pin "2") (pinfunction "2_2") (pintype "passive"))
      (node (ref "C3") (pin "2") (pinfunction "2_2") (pintype "passive"))
      (node (ref "C7") (pin "1") (pinfunction "1_1") (pintype "passive"))
      (node (ref "C8") (pin "1") (pinfunction "1_1") (pintype "passive"))
      (node (ref "C9") (pin "1") (pinfunction "1_1") (pintype "passive"))
      (node (ref "D3") (pin "5") (pinfunction "VM_5") (pintype "passive"))
      (node (ref "D4") (pin "5") (pinfunction "VM_5") (pintype "passive"))
      (node (ref "D5") (pin "5") (pinfunction "VM_5") (pintype "passive"))
      (node (ref "D6") (pin "5") (pinfunction "VM_5") (pintype "passive"))
      (node (ref "D7") (pin "5") (pinfunction "VM_5") (pintype "passive"))
      (node (ref "D8") (pin "5") (pinfunction "VM_5") (pintype "passive"))
      (node (ref "D9") (pin "7") (pinfunction "VIN_7") (pintype "passive"))
      (node (ref "R5") (pin "2") (pinfunction "2_2") (pintype "passive"))
      (node (ref "X1") (pin "1") (pinfunction "1_1") (pintype "passive"))
      (node (ref "X12") (pin "1") (pinfunction "1_1") (pintype "passive"))
      (node (ref "X5") (pin "1") (pinfunction "1_1") (pintype "passive"))
    )
    (net (code "65") (name "unconnected-(D2-0_RX0_PCINT8_PE8-Pad2)") (class "Default")
      (node (ref "D2") (pin "2") (pinfunction "0_RX0_PCINT8_PE8_2") (pintype "passive"))
    )
    (net (code "66") (name "unconnected-(D2-1_TX0_PE1-Pad3)") (class "Default")
      (node (ref "D2") (pin "3") (pinfunction "1_TX0_PE1_3") (pintype "passive"))
    )
    (net (code "67") (name "unconnected-(D2-3V3-Pad74)") (class "Default")
      (node (ref "D2") (pin "74") (pinfunction "3V3_74") (pintype "passive"))
    )
    (net (code "68") (name "unconnected-(D2-32_PC5_A13-Pad34)") (class "Default")
      (node (ref "D2") (pin "34") (pinfunction "32_PC5_A13_34") (pintype "passive"))
    )
    (net (code "69") (name "unconnected-(D2-33_PC4_A12-Pad35)") (class "Default")
      (node (ref "D2") (pin "35") (pinfunction "33_PC4_A12_35") (pintype "passive"))
    )
    (net (code "70") (name "unconnected-(D2-34_PC3_A11-Pad36)") (class "Default")
      (node (ref "D2") (pin "36") (pinfunction "34_PC3_A11_36") (pintype "passive"))
    )
    (net (code "71") (name "unconnected-(D2-35_PC2_A10-Pad37)") (class "Default")
      (node (ref "D2") (pin "37") (pinfunction "35_PC2_A10_37") (pintype "passive"))
    )
    (net (code "72") (name "unconnected-(D2-37_PC0_A8-Pad39)") (class "Default")
      (node (ref "D2") (pin "39") (pinfunction "37_PC0_A8_39") (pintype "passive"))
    )
    (net (code "73") (name "unconnected-(D2-38_PD7_T0-Pad40)") (class "Default")
      (node (ref "D2") (pin "40") (pinfunction "38_PD7_T0_40") (pintype "passive"))
    )
    (net (code "74") (name "unconnected-(D2-39_PG2_ALE-Pad41)") (class "Default")
      (node (ref "D2") (pin "41") (pinfunction "39_PG2_ALE_41") (pintype "passive"))
    )
    (net (code "75") (name "unconnected-(D2-40_PG1_RD-Pad42)") (class "Default")
      (node (ref "D2") (pin "42") (pinfunction "40_PG1_RD_42") (pintype "passive"))
    )
    (net (code "76") (name "unconnected-(D2-41_PG0_WR-Pad43)") (class "Default")
      (node (ref "D2") (pin "43") (pinfunction "41_PG0_WR_43") (pintype "passive"))
    )
    (net (code "77") (name "unconnected-(D2-42_PL7-Pad44)") (class "Default")
      (node (ref "D2") (pin "44") (pinfunction "42_PL7_44") (pintype "passive"))
    )
    (net (code "78") (name "unconnected-(D2-43_PL6-Pad45)") (class "Default")
      (node (ref "D2") (pin "45") (pinfunction "43_PL6_45") (pintype "passive"))
    )
    (net (code "79") (name "unconnected-(D2-44_PL5_OC5C-Pad46)") (class "Default")
      (node (ref "D2") (pin "46") (pinfunction "44_PL5_OC5C_46") (pintype "passive"))
    )
    (net (code "80") (name "unconnected-(D2-45_PL4_OC5B-Pad47)") (class "Default")
      (node (ref "D2") (pin "47") (pinfunction "45_PL4_OC5B_47") (pintype "passive"))
    )
    (net (code "81") (name "unconnected-(D2-46_PL3_OC5A-Pad48)") (class "Default")
      (node (ref "D2") (pin "48") (pinfunction "46_PL3_OC5A_48") (pintype "passive"))
    )
    (net (code "82") (name "unconnected-(D2-47_PL2_T5-Pad49)") (class "Default")
      (node (ref "D2") (pin "49") (pinfunction "47_PL2_T5_49") (pintype "passive"))
    )
    (net (code "83") (name "unconnected-(D2-48_PL1_IC5P-Pad50)") (class "Default")
      (node (ref "D2") (pin "50") (pinfunction "48_PL1_IC5P_50") (pintype "passive"))
    )
    (net (code "84") (name "unconnected-(D2-49_PL0_ICP4-Pad51)") (class "Default")
      (node (ref "D2") (pin "51") (pinfunction "49_PL0_ICP4_51") (pintype "passive"))
    )
    (net (code "85") (name "unconnected-(D2-53_SS_PB0_PCINT0-Pad55)") (class "Default")
      (node (ref "D2") (pin "55") (pinfunction "53_SS_PB0_PCINT0_55") (pintype "passive"))
    )
    (net (code "86") (name "unconnected-(D2-A2{slash}56_PF2_ADC2-Pad58)") (class "Default")
      (node (ref "D2") (pin "58") (pinfunction "A2/56_PF2_ADC2_58") (pintype "passive"))
    )
    (net (code "87") (name "unconnected-(D2-A3{slash}57_PF3_ADC3_TCK-Pad59)") (class "Default")
      (node (ref "D2") (pin "59") (pinfunction "A3/57_PF3_ADC3_TCK_59") (pintype "passive"))
    )
    (net (code "88") (name "unconnected-(D2-A4{slash}58_PF4_ADC3_TCK-Pad60)") (class "Default")
      (node (ref "D2") (pin "60") (pinfunction "A4/58_PF4_ADC3_TCK_60") (pintype "passive"))
    )
    (net (code "89") (name "unconnected-(D2-A5{slash}59_PF5_ADC4_TMS-Pad61)") (class "Default")
      (node (ref "D2") (pin "61") (pinfunction "A5/59_PF5_ADC4_TMS_61") (pintype "passive"))
    )
    (net (code "90") (name "unconnected-(D2-A6{slash}60_PF6_ADC6_TDO-Pad62)") (class "Default")
      (node (ref "D2") (pin "62") (pinfunction "A6/60_PF6_ADC6_TDO_62") (pintype "passive"))
    )
    (net (code "91") (name "unconnected-(D2-A7{slash}61_PF7_ADC7_TDI-Pad63)") (class "Default")
      (node (ref "D2") (pin "63") (pinfunction "A7/61_PF7_ADC7_TDI_63") (pintype "passive"))
    )
    (net (code "92") (name "unconnected-(D2-A8{slash}62_PK0_ADC8_PCINT16-Pad64)") (class "Default")
      (node (ref "D2") (pin "64") (pinfunction "A8/62_PK0_ADC8_PCINT16_64") (pintype "passive"))
    )
    (net (code "93") (name "unconnected-(D2-A9{slash}63_PK1_ADC9_PCINT17-Pad65)") (class "Default")
      (node (ref "D2") (pin "65") (pinfunction "A9/63_PK1_ADC9_PCINT17_65") (pintype "passive"))
    )
    (net (code "94") (name "unconnected-(D2-A10{slash}64_PK2_ADC10_PCINT18-Pad66)") (class "Default")
      (node (ref "D2") (pin "66") (pinfunction "A10/64_PK2_ADC10_PCINT18_66") (pintype "passive"))
    )
    (net (code "95") (name "unconnected-(D2-A11{slash}65_PK3_ADC11_PCINT19-Pad67)") (class "Default")
      (node (ref "D2") (pin "67") (pinfunction "A11/65_PK3_ADC11_PCINT19_67") (pintype "passive"))
    )
    (net (code "96") (name "unconnected-(D2-A12{slash}66_PK4_ADC12_PCINT20-Pad68)") (class "Default")
      (node (ref "D2") (pin "68") (pinfunction "A12/66_PK4_ADC12_PCINT20_68") (pintype "passive"))
    )
    (net (code "97") (name "unconnected-(D2-A13{slash}66_PK5_ADC13_PCINT21-Pad69)") (class "Default")
      (node (ref "D2") (pin "69") (pinfunction "A13/66_PK5_ADC13_PCINT21_69") (pintype "passive"))
    )
    (net (code "98") (name "unconnected-(D2-A14{slash}67_PK5_ADC14_PCINT22-Pad70)") (class "Default")
      (node (ref "D2") (pin "70") (pinfunction "A14/67_PK5_ADC14_PCINT22_70") (pintype "passive"))
    )
    (net (code "99") (name "unconnected-(D2-A15{slash}67_PK6_ADC14_PCINT22-Pad71)") (class "Default")
      (node (ref "D2") (pin "71") (pinfunction "A15/67_PK6_ADC14_PCINT22_71") (pintype "passive"))
    )
    (net (code "100") (name "unconnected-(D2-AREF-Pad0)") (class "Default")
      (node (ref "D2") (pin "0") (pinfunction "AREF_0") (pintype "passive"))
    )
    (net (code "101") (name "unconnected-(D2-GND-Pad75)") (class "Default")
      (node (ref "D2") (pin "75") (pinfunction "GND_75") (pintype "passive"))
    )
    (net (code "102") (name "unconnected-(D2-RESET-Pad1)") (class "Default")
      (node (ref "D2") (pin "1") (pinfunction "RESET_1") (pintype "passive"))
    )
    (net (code "103") (name "unconnected-(D2-VIN-Pad72)") (class "Default")
      (node (ref "D2") (pin "72") (pinfunction "VIN_72") (pintype "passive"))
    )
    (net (code "104") (name "unconnected-(N1-Pad8)") (class "Default")
      (node (ref "N1") (pin "8") (pinfunction "8_8") (pintype "passive"))
    )
    (net (code "105") (name "unconnected-(SB1-GND-Pad3)") (class "Default")
      (node (ref "SB1") (pin "3") (pinfunction "GND_3") (pintype "passive"))
    )
    (net (code "106") (name "unconnected-(SB2-GND-Pad3)") (class "Default")
      (node (ref "SB2") (pin "3") (pinfunction "GND_3") (pintype "passive"))
    )
    (net (code "107") (name "unconnected-(SB3-GND-Pad3)") (class "Default")
      (node (ref "SB3") (pin "3") (pinfunction "GND_3") (pintype "passive"))
    )
    (net (code "108") (name "unconnected-(X7-Pad5)") (class "Default")
      (node (ref "X7") (pin "5") (pinfunction "5_5") (pintype "passive"))
    )
    (net (code "109") (name "unconnected-(X7-Pad6)") (class "Default")
      (node (ref "X7") (pin "6") (pinfunction "6_6") (pintype "passive"))
    )
    (net (code "110") (name "unconnected-(X7-Pad8)") (class "Default")
      (node (ref "X7") (pin "8") (pinfunction "8_8") (pintype "passive"))
    )
    (net (code "111") (name "unconnected-(X7-Pad10)") (class "Default")
      (node (ref "X7") (pin "10") (pinfunction "10_10") (pintype "passive"))
    )
  )
)
